# plytka_v3.net
KiCad netlist of a schematic drawn in EAGLE
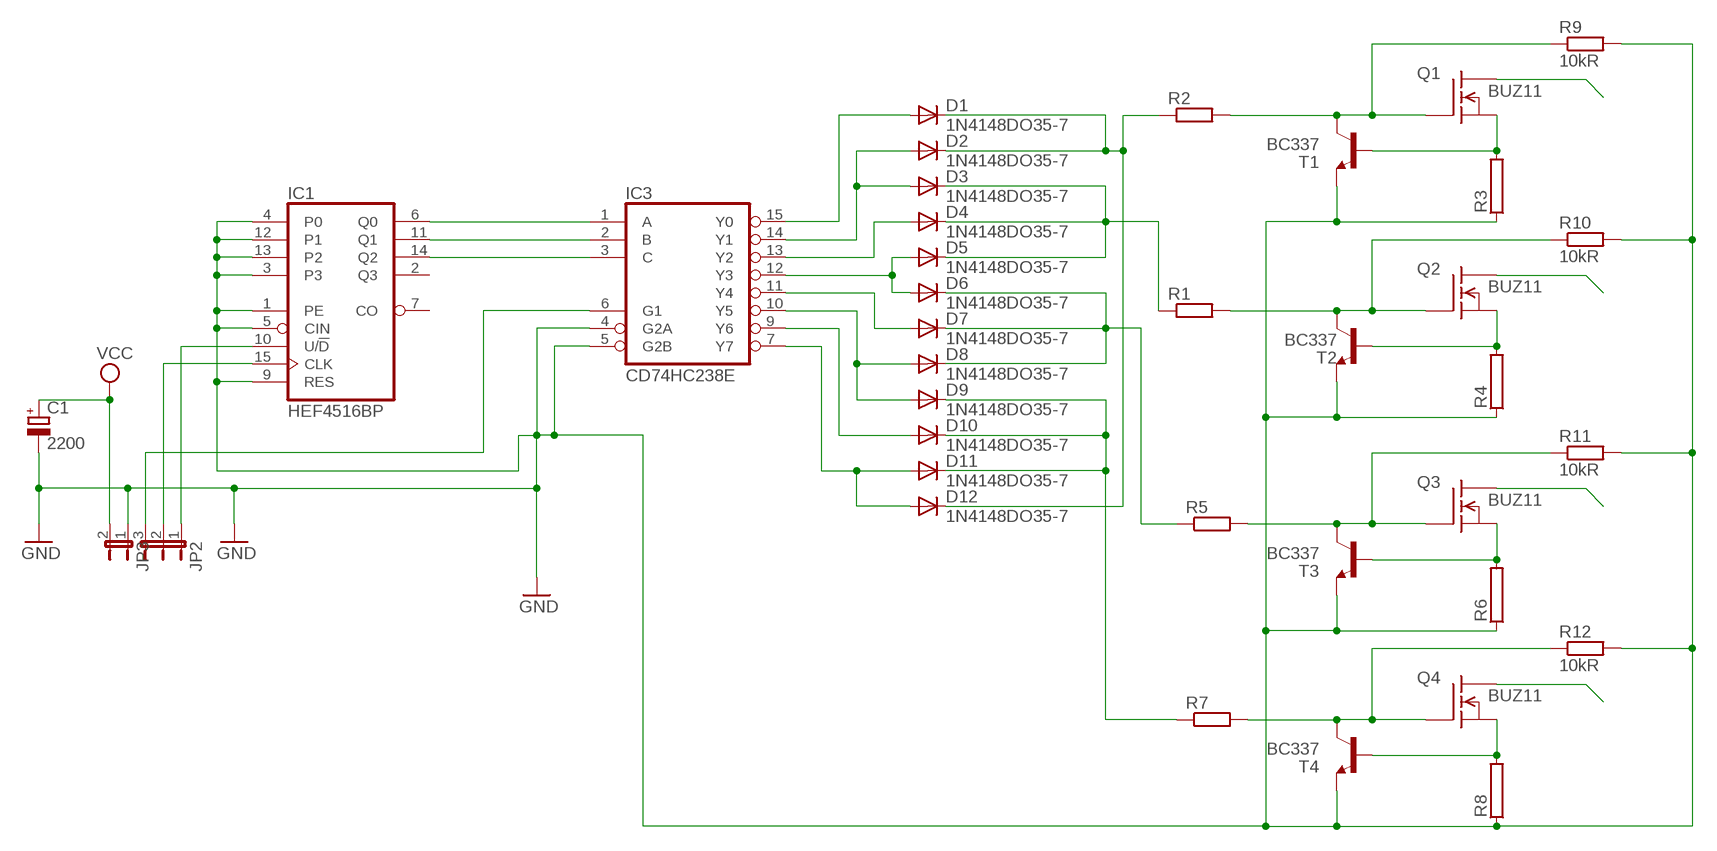
[diagram p0: schematic, sheet 1]

(export (version "E")
  (design (tool "Eeschema 10.0.6"))
  (components
    (comp (ref "C1")
      (value "2200")
      (footprint "eagle-import:E5-10,5")
      (libsource (lib "eagle-import") (part "CPOL-EUE5-10.5"))
    )
    (comp (ref "D1")
      (value "1N4148DO35-7")
      (footprint "eagle-import:DO35-7")
      (libsource (lib "eagle-import") (part "1N4148DO35-7"))
    )
    (comp (ref "D2")
      (value "1N4148DO35-7")
      (footprint "eagle-import:DO35-7")
      (libsource (lib "eagle-import") (part "1N4148DO35-7"))
    )
    (comp (ref "D3")
      (value "1N4148DO35-7")
      (footprint "eagle-import:DO35-7")
      (libsource (lib "eagle-import") (part "1N4148DO35-7"))
    )
    (comp (ref "D4")
      (value "1N4148DO35-7")
      (footprint "eagle-import:DO35-7")
      (libsource (lib "eagle-import") (part "1N4148DO35-7"))
    )
    (comp (ref "D5")
      (value "1N4148DO35-7")
      (footprint "eagle-import:DO35-7")
      (libsource (lib "eagle-import") (part "1N4148DO35-7"))
    )
    (comp (ref "D6")
      (value "1N4148DO35-7")
      (footprint "eagle-import:DO35-7")
      (libsource (lib "eagle-import") (part "1N4148DO35-7"))
    )
    (comp (ref "D7")
      (value "1N4148DO35-7")
      (footprint "eagle-import:DO35-7")
      (libsource (lib "eagle-import") (part "1N4148DO35-7"))
    )
    (comp (ref "D8")
      (value "1N4148DO35-7")
      (footprint "eagle-import:DO35-7")
      (libsource (lib "eagle-import") (part "1N4148DO35-7"))
    )
    (comp (ref "D9")
      (value "1N4148DO35-7")
      (footprint "eagle-import:DO35-7")
      (libsource (lib "eagle-import") (part "1N4148DO35-7"))
    )
    (comp (ref "D10")
      (value "1N4148DO35-7")
      (footprint "eagle-import:DO35-7")
      (libsource (lib "eagle-import") (part "1N4148DO35-7"))
    )
    (comp (ref "D11")
      (value "1N4148DO35-7")
      (footprint "eagle-import:DO35-7")
      (libsource (lib "eagle-import") (part "1N4148DO35-7"))
    )
    (comp (ref "D12")
      (value "1N4148DO35-7")
      (footprint "eagle-import:DO35-7")
      (libsource (lib "eagle-import") (part "1N4148DO35-7"))
    )
    (comp (ref "IC1")
      (value "HEF4516BP")
      (footprint "eagle-import:DIL16")
      (libsource (lib "eagle-import") (part "4516N"))
    )
    (comp (ref "IC3")
      (value "CD74HC238E")
      (footprint "eagle-import:DIL16")
      (libsource (lib "eagle-import") (part "74138NAC"))
    )
    (comp (ref "JP2")
      (value "JP2E")
      (footprint "eagle-import:JP2")
      (libsource (lib "eagle-import") (part "JP2E"))
    )
    (comp (ref "JP3")
      (value "JP1E")
      (footprint "eagle-import:JP1")
      (libsource (lib "eagle-import") (part "JP1E"))
    )
    (comp (ref "Q1")
      (value "BUZ11")
      (footprint "eagle-import:TO220")
      (libsource (lib "eagle-import") (part "BUZ11"))
    )
    (comp (ref "Q2")
      (value "BUZ11")
      (footprint "eagle-import:TO220")
      (libsource (lib "eagle-import") (part "BUZ11"))
    )
    (comp (ref "Q3")
      (value "BUZ11")
      (footprint "eagle-import:TO220")
      (libsource (lib "eagle-import") (part "BUZ11"))
    )
    (comp (ref "Q4")
      (value "BUZ11")
      (footprint "eagle-import:TO220")
      (libsource (lib "eagle-import") (part "BUZ11"))
    )
    (comp (ref "R1")
      (value "R-EU_0207/15")
      (footprint "eagle-import:0207_15")
      (libsource (lib "eagle-import") (part "R-EU_0207/15"))
    )
    (comp (ref "R2")
      (value "R-EU_0207/15")
      (footprint "eagle-import:0207_15")
      (libsource (lib "eagle-import") (part "R-EU_0207/15"))
    )
    (comp (ref "R3")
      (value "RKH208-8R")
      (footprint "eagle-import:KH208R-8")
      (libsource (lib "eagle-import") (part "RKH208-8R"))
    )
    (comp (ref "R4")
      (value "RKH208-8R")
      (footprint "eagle-import:KH208R-8")
      (libsource (lib "eagle-import") (part "RKH208-8R"))
    )
    (comp (ref "R5")
      (value "R-EU_0207/15")
      (footprint "eagle-import:0207_15")
      (libsource (lib "eagle-import") (part "R-EU_0207/15"))
    )
    (comp (ref "R6")
      (value "RKH208-8R")
      (footprint "eagle-import:KH208R-8")
      (libsource (lib "eagle-import") (part "RKH208-8R"))
    )
    (comp (ref "R7")
      (value "R-EU_0207/15")
      (footprint "eagle-import:0207_15")
      (libsource (lib "eagle-import") (part "R-EU_0207/15"))
    )
    (comp (ref "R8")
      (value "RKH208-8R")
      (footprint "eagle-import:KH208R-8")
      (libsource (lib "eagle-import") (part "RKH208-8R"))
    )
    (comp (ref "R9")
      (value "10kR")
      (footprint "eagle-import:0207_7")
      (libsource (lib "eagle-import") (part "R-EU_0207/7"))
    )
    (comp (ref "R10")
      (value "10kR")
      (footprint "eagle-import:0207_7")
      (libsource (lib "eagle-import") (part "R-EU_0207/7"))
    )
    (comp (ref "R11")
      (value "10kR")
      (footprint "eagle-import:0207_7")
      (libsource (lib "eagle-import") (part "R-EU_0207/7"))
    )
    (comp (ref "R12")
      (value "10kR")
      (footprint "eagle-import:0207_7")
      (libsource (lib "eagle-import") (part "R-EU_0207/7"))
    )
    (comp (ref "T1")
      (value "BC337")
      (footprint "eagle-import:TO92")
      (libsource (lib "eagle-import") (part "BC337"))
    )
    (comp (ref "T2")
      (value "BC337")
      (footprint "eagle-import:TO92")
      (libsource (lib "eagle-import") (part "BC337"))
    )
    (comp (ref "T3")
      (value "BC337")
      (footprint "eagle-import:TO92")
      (libsource (lib "eagle-import") (part "BC337"))
    )
    (comp (ref "T4")
      (value "BC337")
      (footprint "eagle-import:TO92")
      (libsource (lib "eagle-import") (part "BC337"))
    )
  )
  (nets
    (net (code "1") (name "GND") (class "Default")
      (node (ref "C1") (pin "-") (pinfunction "-_-") (pintype "passive"))
      (node (ref "IC1") (pin "1") (pinfunction "PE_1") (pintype "input"))
      (node (ref "IC1") (pin "12") (pinfunction "P1_12") (pintype "input"))
      (node (ref "IC1") (pin "13") (pinfunction "P2_13") (pintype "input"))
      (node (ref "IC1") (pin "3") (pinfunction "P3_3") (pintype "input"))
      (node (ref "IC1") (pin "4") (pinfunction "P0_4") (pintype "input"))
      (node (ref "IC1") (pin "5") (pinfunction "CIN_5") (pintype "input"))
      (node (ref "IC1") (pin "9") (pinfunction "RES_9") (pintype "input"))
      (node (ref "IC3") (pin "4") (pinfunction "G2A_4") (pintype "input"))
      (node (ref "IC3") (pin "5") (pinfunction "G2B_5") (pintype "input"))
      (node (ref "JP3") (pin "1") (pinfunction "1_1") (pintype "passive"))
      (node (ref "R10") (pin "2") (pinfunction "2_2") (pintype "passive"))
      (node (ref "R11") (pin "2") (pinfunction "2_2") (pintype "passive"))
      (node (ref "R12") (pin "2") (pinfunction "2_2") (pintype "passive"))
      (node (ref "R3") (pin "1") (pinfunction "1_1") (pintype "passive"))
      (node (ref "R4") (pin "1") (pinfunction "1_1") (pintype "passive"))
      (node (ref "R6") (pin "1") (pinfunction "1_1") (pintype "passive"))
      (node (ref "R8") (pin "1") (pinfunction "1_1") (pintype "passive"))
      (node (ref "R9") (pin "2") (pinfunction "2_2") (pintype "passive"))
      (node (ref "T1") (pin "1") (pinfunction "E_1") (pintype "passive"))
      (node (ref "T2") (pin "1") (pinfunction "E_1") (pintype "passive"))
      (node (ref "T3") (pin "1") (pinfunction "E_1") (pintype "passive"))
      (node (ref "T4") (pin "1") (pinfunction "E_1") (pintype "passive"))
    )
    (net (code "2") (name "Net-(D1-PadC)") (class "Default")
      (node (ref "D1") (pin "C") (pinfunction "C_C") (pintype "passive"))
      (node (ref "D12") (pin "C") (pinfunction "C_C") (pintype "passive"))
      (node (ref "D2") (pin "C") (pinfunction "C_C") (pintype "passive"))
      (node (ref "R2") (pin "1") (pinfunction "1_1") (pintype "passive"))
    )
    (net (code "3") (name "Net-(D3-PadC)") (class "Default")
      (node (ref "D3") (pin "C") (pinfunction "C_C") (pintype "passive"))
      (node (ref "D4") (pin "C") (pinfunction "C_C") (pintype "passive"))
      (node (ref "D5") (pin "C") (pinfunction "C_C") (pintype "passive"))
      (node (ref "R1") (pin "1") (pinfunction "1_1") (pintype "passive"))
    )
    (net (code "4") (name "Net-(D6-PadC)") (class "Default")
      (node (ref "D6") (pin "C") (pinfunction "C_C") (pintype "passive"))
      (node (ref "D7") (pin "C") (pinfunction "C_C") (pintype "passive"))
      (node (ref "D8") (pin "C") (pinfunction "C_C") (pintype "passive"))
      (node (ref "R5") (pin "1") (pinfunction "1_1") (pintype "passive"))
    )
    (net (code "5") (name "Net-(D10-PadC)") (class "Default")
      (node (ref "D10") (pin "C") (pinfunction "C_C") (pintype "passive"))
      (node (ref "D11") (pin "C") (pinfunction "C_C") (pintype "passive"))
      (node (ref "D9") (pin "C") (pinfunction "C_C") (pintype "passive"))
      (node (ref "R7") (pin "1") (pinfunction "1_1") (pintype "passive"))
    )
    (net (code "6") (name "Net-(IC1A-CLK)") (class "Default")
      (node (ref "IC1") (pin "15") (pinfunction "CLK_15") (pintype "input"))
      (node (ref "JP2") (pin "2") (pinfunction "2_2") (pintype "passive"))
    )
    (net (code "7") (name "Net-(IC1A-Q0)") (class "Default")
      (node (ref "IC1") (pin "6") (pinfunction "Q0_6") (pintype "output"))
      (node (ref "IC3") (pin "1") (pinfunction "A_1") (pintype "input"))
    )
    (net (code "8") (name "Net-(IC1A-Q1)") (class "Default")
      (node (ref "IC1") (pin "11") (pinfunction "Q1_11") (pintype "output"))
      (node (ref "IC3") (pin "2") (pinfunction "B_2") (pintype "input"))
    )
    (net (code "9") (name "Net-(IC1A-Q2)") (class "Default")
      (node (ref "IC1") (pin "14") (pinfunction "Q2_14") (pintype "output"))
      (node (ref "IC3") (pin "3") (pinfunction "C_3") (pintype "input"))
    )
    (net (code "10") (name "Net-(IC1A-U{slash}~{D})") (class "Default")
      (node (ref "IC1") (pin "10") (pinfunction "U/~{D}_10") (pintype "input"))
      (node (ref "JP2") (pin "1") (pinfunction "1_1") (pintype "passive"))
    )
    (net (code "11") (name "Net-(IC3A-G1)") (class "Default")
      (node (ref "IC3") (pin "6") (pinfunction "G1_6") (pintype "input"))
      (node (ref "JP2") (pin "3") (pinfunction "3_3") (pintype "passive"))
    )
    (net (code "12") (name "Net-(IC3A-Y0)") (class "Default")
      (node (ref "D1") (pin "A") (pinfunction "A_A") (pintype "passive"))
      (node (ref "IC3") (pin "15") (pinfunction "Y0_15") (pintype "output"))
    )
    (net (code "13") (name "Net-(IC3A-Y1)") (class "Default")
      (node (ref "D2") (pin "A") (pinfunction "A_A") (pintype "passive"))
      (node (ref "D3") (pin "A") (pinfunction "A_A") (pintype "passive"))
      (node (ref "IC3") (pin "14") (pinfunction "Y1_14") (pintype "output"))
    )
    (net (code "14") (name "Net-(IC3A-Y2)") (class "Default")
      (node (ref "D4") (pin "A") (pinfunction "A_A") (pintype "passive"))
      (node (ref "IC3") (pin "13") (pinfunction "Y2_13") (pintype "output"))
    )
    (net (code "15") (name "Net-(IC3A-Y3)") (class "Default")
      (node (ref "D5") (pin "A") (pinfunction "A_A") (pintype "passive"))
      (node (ref "D6") (pin "A") (pinfunction "A_A") (pintype "passive"))
      (node (ref "IC3") (pin "12") (pinfunction "Y3_12") (pintype "output"))
    )
    (net (code "16") (name "Net-(IC3A-Y4)") (class "Default")
      (node (ref "D7") (pin "A") (pinfunction "A_A") (pintype "passive"))
      (node (ref "IC3") (pin "11") (pinfunction "Y4_11") (pintype "output"))
    )
    (net (code "17") (name "Net-(IC3A-Y5)") (class "Default")
      (node (ref "D8") (pin "A") (pinfunction "A_A") (pintype "passive"))
      (node (ref "D9") (pin "A") (pinfunction "A_A") (pintype "passive"))
      (node (ref "IC3") (pin "10") (pinfunction "Y5_10") (pintype "output"))
    )
    (net (code "18") (name "Net-(IC3A-Y6)") (class "Default")
      (node (ref "D10") (pin "A") (pinfunction "A_A") (pintype "passive"))
      (node (ref "IC3") (pin "9") (pinfunction "Y6_9") (pintype "output"))
    )
    (net (code "19") (name "Net-(IC3A-Y7)") (class "Default")
      (node (ref "D11") (pin "A") (pinfunction "A_A") (pintype "passive"))
      (node (ref "D12") (pin "A") (pinfunction "A_A") (pintype "passive"))
      (node (ref "IC3") (pin "7") (pinfunction "Y7_7") (pintype "output"))
    )
    (net (code "20") (name "Net-(Q1-G)") (class "Default")
      (node (ref "Q1") (pin "1") (pinfunction "G_1") (pintype "passive"))
      (node (ref "R2") (pin "2") (pinfunction "2_2") (pintype "passive"))
      (node (ref "R9") (pin "1") (pinfunction "1_1") (pintype "passive"))
      (node (ref "T1") (pin "3") (pinfunction "C_3") (pintype "passive"))
    )
    (net (code "21") (name "Net-(Q1-S)") (class "Default")
      (node (ref "Q1") (pin "3") (pinfunction "S_3") (pintype "passive"))
      (node (ref "R3") (pin "2") (pinfunction "2_2") (pintype "passive"))
      (node (ref "T1") (pin "2") (pinfunction "B_2") (pintype "passive"))
    )
    (net (code "22") (name "Net-(Q2-G)") (class "Default")
      (node (ref "Q2") (pin "1") (pinfunction "G_1") (pintype "passive"))
      (node (ref "R1") (pin "2") (pinfunction "2_2") (pintype "passive"))
      (node (ref "R10") (pin "1") (pinfunction "1_1") (pintype "passive"))
      (node (ref "T2") (pin "3") (pinfunction "C_3") (pintype "passive"))
    )
    (net (code "23") (name "Net-(Q2-S)") (class "Default")
      (node (ref "Q2") (pin "3") (pinfunction "S_3") (pintype "passive"))
      (node (ref "R4") (pin "2") (pinfunction "2_2") (pintype "passive"))
      (node (ref "T2") (pin "2") (pinfunction "B_2") (pintype "passive"))
    )
    (net (code "24") (name "Net-(Q3-G)") (class "Default")
      (node (ref "Q3") (pin "1") (pinfunction "G_1") (pintype "passive"))
      (node (ref "R11") (pin "1") (pinfunction "1_1") (pintype "passive"))
      (node (ref "R5") (pin "2") (pinfunction "2_2") (pintype "passive"))
      (node (ref "T3") (pin "3") (pinfunction "C_3") (pintype "passive"))
    )
    (net (code "25") (name "Net-(Q3-S)") (class "Default")
      (node (ref "Q3") (pin "3") (pinfunction "S_3") (pintype "passive"))
      (node (ref "R6") (pin "2") (pinfunction "2_2") (pintype "passive"))
      (node (ref "T3") (pin "2") (pinfunction "B_2") (pintype "passive"))
    )
    (net (code "26") (name "Net-(Q4-G)") (class "Default")
      (node (ref "Q4") (pin "1") (pinfunction "G_1") (pintype "passive"))
      (node (ref "R12") (pin "1") (pinfunction "1_1") (pintype "passive"))
      (node (ref "R7") (pin "2") (pinfunction "2_2") (pintype "passive"))
      (node (ref "T4") (pin "3") (pinfunction "C_3") (pintype "passive"))
    )
    (net (code "27") (name "Net-(Q4-S)") (class "Default")
      (node (ref "Q4") (pin "3") (pinfunction "S_3") (pintype "passive"))
      (node (ref "R8") (pin "2") (pinfunction "2_2") (pintype "passive"))
      (node (ref "T4") (pin "2") (pinfunction "B_2") (pintype "passive"))
    )
    (net (code "28") (name "VCC") (class "Default")
      (node (ref "C1") (pin "+") (pinfunction "+_+") (pintype "passive"))
      (node (ref "JP3") (pin "2") (pinfunction "2_2") (pintype "passive"))
    )
    (net (code "29") (name "unconnected-(IC1A-CO-Pad7)") (class "Default")
      (node (ref "IC1") (pin "7") (pinfunction "CO_7") (pintype "output"))
    )
    (net (code "30") (name "unconnected-(IC1A-Q3-Pad2)") (class "Default")
      (node (ref "IC1") (pin "2") (pinfunction "Q3_2") (pintype "output"))
    )
    (net (code "31") (name "unconnected-(Q1-D-Pad2)") (class "Default")
      (node (ref "Q1") (pin "2") (pinfunction "D_2") (pintype "passive"))
    )
    (net (code "32") (name "unconnected-(Q2-D-Pad2)") (class "Default")
      (node (ref "Q2") (pin "2") (pinfunction "D_2") (pintype "passive"))
    )
    (net (code "33") (name "unconnected-(Q3-D-Pad2)") (class "Default")
      (node (ref "Q3") (pin "2") (pinfunction "D_2") (pintype "passive"))
    )
    (net (code "34") (name "unconnected-(Q4-D-Pad2)") (class "Default")
      (node (ref "Q4") (pin "2") (pinfunction "D_2") (pintype "passive"))
    )
  )
)
